# test.net
KiCad netlist of a schematic drawn in EAGLE
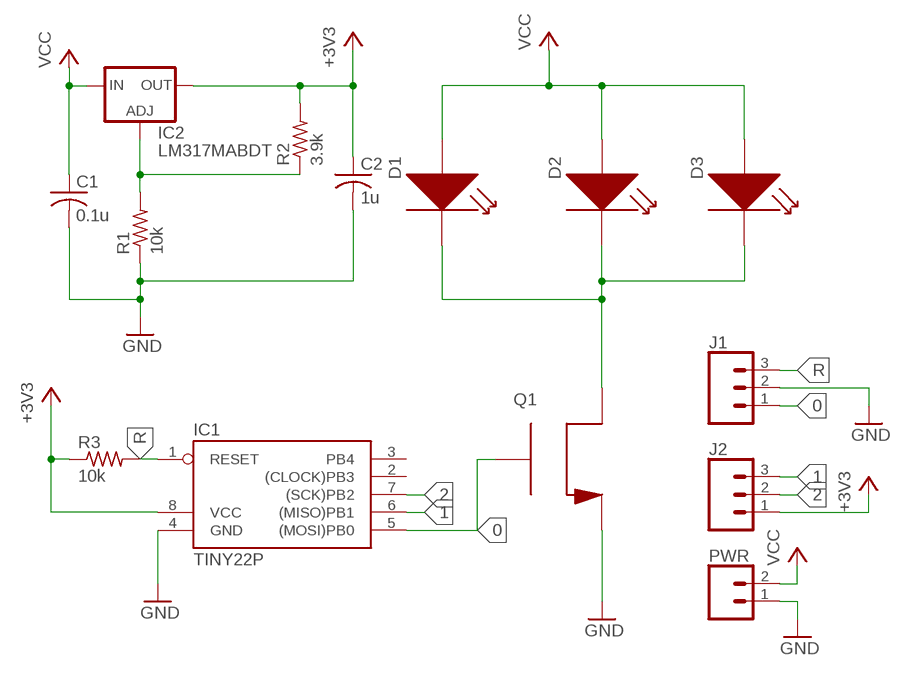
[diagram p0: schematic, sheet 1]

(export (version "E")
  (design (tool "Eeschema 10.0.6"))
  (components
    (comp (ref "C1")
      (value "0.1u")
      (footprint "eagle-import:C025-024X044")
      (libsource (lib "eagle-import") (part "C-US025-024X044"))
    )
    (comp (ref "C2")
      (value "1u")
      (footprint "eagle-import:C025-024X044")
      (libsource (lib "eagle-import") (part "C-US025-024X044"))
    )
    (comp (ref "D1")
      (value "NVSLE21AT")
      (footprint "eagle-import:NVSLE21AT")
      (libsource (lib "eagle-import") (part "NVSLE21AT"))
    )
    (comp (ref "D2")
      (value "NVSLE21AT")
      (footprint "eagle-import:NVSLE21AT")
      (libsource (lib "eagle-import") (part "NVSLE21AT"))
    )
    (comp (ref "D3")
      (value "NVSLE21AT")
      (footprint "eagle-import:NVSLE21AT")
      (libsource (lib "eagle-import") (part "NVSLE21AT"))
    )
    (comp (ref "IC1")
      (value "TINY22P")
      (footprint "eagle-import:DIL08")
      (libsource (lib "eagle-import") (part "TINY22P"))
    )
    (comp (ref "IC2")
      (value "LM317MABDT")
      (footprint "eagle-import:DPACK")
      (libsource (lib "eagle-import") (part "v-reg_409_LM317?MABDT"))
    )
    (comp (ref "J1")
      (value "CONN_03")
      (footprint "eagle-import:1X03")
      (libsource (lib "eagle-import") (part "CONN_03"))
    )
    (comp (ref "J2")
      (value "CONN_03")
      (footprint "eagle-import:1X03")
      (libsource (lib "eagle-import") (part "CONN_03"))
    )
    (comp (ref "PWR")
      (value "CONN_02")
      (footprint "eagle-import:1X02")
      (libsource (lib "eagle-import") (part "CONN_02"))
    )
    (comp (ref "Q1")
      (value "SIA436DJ")
      (footprint "eagle-import:POWERPAK_SC70-6L")
      (libsource (lib "eagle-import") (part "SIA436DJ"))
    )
    (comp (ref "R1")
      (value "10k")
      (footprint "eagle-import:0204_5")
      (libsource (lib "eagle-import") (part "R-US_0204/5"))
    )
    (comp (ref "R2")
      (value "3.9k")
      (footprint "eagle-import:0204_5")
      (libsource (lib "eagle-import") (part "R-US_0204/5"))
    )
    (comp (ref "R3")
      (value "10k")
      (footprint "eagle-import:0204_5")
      (libsource (lib "eagle-import") (part "R-US_0204/5"))
    )
  )
  (nets
    (net (code "1") (name "+3V3") (class "Default")
      (node (ref "C2") (pin "1") (pinfunction "1_1") (pintype "passive"))
      (node (ref "IC1") (pin "8") (pinfunction "VCC_8") (pintype "power_in"))
      (node (ref "IC2") (pin "4") (pinfunction "OUT_4") (pintype "passive"))
      (node (ref "J2") (pin "1") (pinfunction "1_1") (pintype "passive"))
      (node (ref "R2") (pin "2") (pinfunction "2_2") (pintype "passive"))
      (node (ref "R3") (pin "1") (pinfunction "1_1") (pintype "passive"))
    )
    (net (code "2") (name "0") (class "Default")
      (node (ref "IC1") (pin "5") (pinfunction "(MOSI)PB0_5") (pintype "bidirectional"))
      (node (ref "J1") (pin "1") (pinfunction "1_1") (pintype "passive"))
      (node (ref "Q1") (pin "P$4") (pinfunction "G_P$4") (pintype "bidirectional"))
    )
    (net (code "3") (name "1") (class "Default")
      (node (ref "IC1") (pin "6") (pinfunction "(MISO)PB1_6") (pintype "bidirectional"))
      (node (ref "J2") (pin "3") (pinfunction "3_3") (pintype "passive"))
    )
    (net (code "4") (name "2") (class "Default")
      (node (ref "IC1") (pin "7") (pinfunction "(SCK)PB2_7") (pintype "bidirectional"))
      (node (ref "J2") (pin "2") (pinfunction "2_2") (pintype "passive"))
    )
    (net (code "5") (name "GND") (class "Default")
      (node (ref "C1") (pin "2") (pinfunction "2_2") (pintype "passive"))
      (node (ref "C2") (pin "2") (pinfunction "2_2") (pintype "passive"))
      (node (ref "IC1") (pin "4") (pinfunction "GND_4") (pintype "power_in"))
      (node (ref "J1") (pin "2") (pinfunction "2_2") (pintype "passive"))
      (node (ref "PWR") (pin "1") (pinfunction "1_1") (pintype "passive"))
      (node (ref "Q1") (pin "P$2") (pinfunction "S_P$2") (pintype "bidirectional"))
      (node (ref "Q1") (pin "P$3") (pinfunction "S_P$3") (pintype "bidirectional"))
      (node (ref "R1") (pin "1") (pinfunction "1_1") (pintype "passive"))
    )
    (net (code "6") (name "Net-(D1-CATHODE)") (class "Default")
      (node (ref "D1") (pin "P$1") (pinfunction "CATHODE_P$1") (pintype "bidirectional"))
      (node (ref "D2") (pin "P$1") (pinfunction "CATHODE_P$1") (pintype "bidirectional"))
      (node (ref "D3") (pin "P$1") (pinfunction "CATHODE_P$1") (pintype "bidirectional"))
      (node (ref "Q1") (pin "P$1") (pinfunction "D_P$1") (pintype "bidirectional"))
      (node (ref "Q1") (pin "P$5") (pinfunction "D_P$5") (pintype "bidirectional"))
      (node (ref "Q1") (pin "P$6") (pinfunction "D_P$6") (pintype "bidirectional"))
      (node (ref "Q1") (pin "P$7") (pinfunction "D_P$7") (pintype "bidirectional"))
      (node (ref "Q1") (pin "P$8") (pinfunction "D_P$8") (pintype "bidirectional"))
    )
    (net (code "7") (name "Net-(IC2-ADJ)") (class "Default")
      (node (ref "IC2") (pin "1") (pinfunction "ADJ_1") (pintype "input"))
      (node (ref "R1") (pin "2") (pinfunction "2_2") (pintype "passive"))
      (node (ref "R2") (pin "1") (pinfunction "1_1") (pintype "passive"))
    )
    (net (code "8") (name "R") (class "Default")
      (node (ref "IC1") (pin "1") (pinfunction "RESET_1") (pintype "input"))
      (node (ref "J1") (pin "3") (pinfunction "3_3") (pintype "passive"))
      (node (ref "R3") (pin "2") (pinfunction "2_2") (pintype "passive"))
    )
    (net (code "9") (name "VCC") (class "Default")
      (node (ref "C1") (pin "1") (pinfunction "1_1") (pintype "passive"))
      (node (ref "D1") (pin "P$2") (pinfunction "ANODE_P$2") (pintype "bidirectional"))
      (node (ref "D2") (pin "P$2") (pinfunction "ANODE_P$2") (pintype "bidirectional"))
      (node (ref "D3") (pin "P$2") (pinfunction "ANODE_P$2") (pintype "bidirectional"))
      (node (ref "IC2") (pin "3") (pinfunction "IN_3") (pintype "input"))
      (node (ref "PWR") (pin "2") (pinfunction "2_2") (pintype "passive"))
    )
    (net (code "10") (name "unconnected-(IC1-(CLOCK)PB3-Pad2)") (class "Default")
      (node (ref "IC1") (pin "2") (pinfunction "(CLOCK)PB3_2") (pintype "bidirectional"))
    )
    (net (code "11") (name "unconnected-(IC1-PB4-Pad3)") (class "Default")
      (node (ref "IC1") (pin "3") (pinfunction "PB4_3") (pintype "bidirectional"))
    )
  )
)
